# I2C_EEPROM.net
KiCad netlist of a schematic drawn in Altium Designer
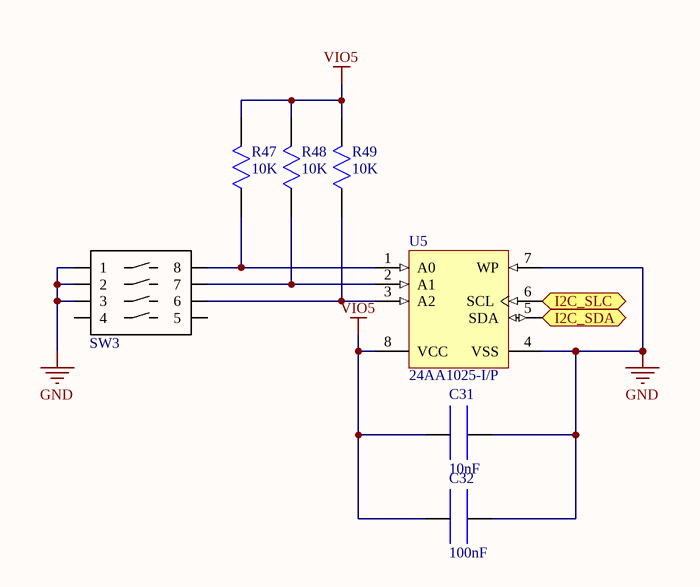
[diagram p0: I2C_EEPROM.SchDoc]

(export (version "E")
  (design (tool "Eeschema 10.0.6"))
  (components
    (comp (ref "C31")
      (value "10nF")
      (footprint "SMD Capacitor 0603")
      (fields (field (name "Comment") "Capacitor"))
      (libsource (lib "DA_Component_Library") (part "Capacitor"))
    )
    (comp (ref "C32")
      (value "100nF")
      (footprint "SMD Capacitor 0603")
      (fields (field (name "Comment") "Capacitor"))
      (libsource (lib "DA_Component_Library") (part "Capacitor"))
    )
    (comp (ref "R47")
      (value "10K")
      (footprint "SMD Resistor 0603")
      (fields (field (name "Comment") "Resistor"))
      (libsource (lib "DA_Component_Library") (part "Resistor"))
    )
    (comp (ref "R48")
      (value "10K")
      (footprint "SMD Resistor 0603")
      (fields (field (name "Comment") "Resistor"))
      (libsource (lib "DA_Component_Library") (part "Resistor"))
    )
    (comp (ref "R49")
      (value "10K")
      (footprint "SMD Resistor 0603")
      (fields (field (name "Comment") "Resistor"))
      (libsource (lib "DA_Component_Library") (part "Resistor"))
    )
    (comp (ref "SW3")
      (value "SW_DIP_4Position")
      (footprint "218-4LPST")
      (libsource (lib "DA_Component_Library") (part "SW_DIP_4Position"))
    )
    (comp (ref "U5")
      (value "24AA1025-I/P")
      (footprint "PDIP300-P8")
      (description "1 Mbit, 400kHz, 1.7V, I2C Serial EEPROM, 8-Pin PDIP, Industrial Temperature")
      (fields (field (name "MANUFACTURER") "Microchip"))
      (libsource (lib "Microchip I2C Serial EEPROM") (part "24AA1025-I/P"))
    )
  )
  (nets
    (net (code "1") (name "/I2C_SDA") (class "Default")
      (node (ref "U5") (pin "5") (pinfunction "SDA_5") (pintype "bidirectional"))
    )
    (net (code "2") (name "/I2C_SLC") (class "Default")
      (node (ref "U5") (pin "6") (pinfunction "SCL_6") (pintype "input"))
    )
    (net (code "3") (name "GND") (class "Default")
      (node (ref "C31") (pin "1") (pinfunction "1_1") (pintype "passive"))
      (node (ref "C32") (pin "1") (pinfunction "1_1") (pintype "passive"))
      (node (ref "SW3") (pin "1") (pinfunction "1_1") (pintype "passive"))
      (node (ref "SW3") (pin "2") (pinfunction "2_2") (pintype "passive"))
      (node (ref "SW3") (pin "3") (pinfunction "3_3") (pintype "passive"))
      (node (ref "U5") (pin "4") (pinfunction "VSS_4") (pintype "power_in"))
      (node (ref "U5") (pin "7") (pinfunction "WP_7") (pintype "input"))
    )
    (net (code "4") (name "Net-(U5-A0)") (class "Default")
      (node (ref "R47") (pin "0") (pinfunction "0_0") (pintype "passive"))
      (node (ref "SW3") (pin "8") (pinfunction "8_8") (pintype "passive"))
      (node (ref "U5") (pin "1") (pinfunction "A0_1") (pintype "input"))
    )
    (net (code "5") (name "Net-(U5-A1)") (class "Default")
      (node (ref "R48") (pin "0") (pinfunction "0_0") (pintype "passive"))
      (node (ref "SW3") (pin "7") (pinfunction "7_7") (pintype "passive"))
      (node (ref "U5") (pin "2") (pinfunction "A1_2") (pintype "input"))
    )
    (net (code "6") (name "Net-(U5-A2)") (class "Default")
      (node (ref "R49") (pin "0") (pinfunction "0_0") (pintype "passive"))
      (node (ref "SW3") (pin "6") (pinfunction "6_6") (pintype "passive"))
      (node (ref "U5") (pin "3") (pinfunction "A2_3") (pintype "input"))
    )
    (net (code "7") (name "VIO5") (class "Default")
      (node (ref "C31") (pin "0") (pinfunction "0_0") (pintype "passive"))
      (node (ref "C32") (pin "0") (pinfunction "0_0") (pintype "passive"))
      (node (ref "R47") (pin "1") (pinfunction "1_1") (pintype "passive"))
      (node (ref "R48") (pin "1") (pinfunction "1_1") (pintype "passive"))
      (node (ref "R49") (pin "1") (pinfunction "1_1") (pintype "passive"))
      (node (ref "U5") (pin "8") (pinfunction "VCC_8") (pintype "power_in"))
    )
    (net (code "8") (name "unconnected-(SW3-Pad4)") (class "Default")
      (node (ref "SW3") (pin "4") (pinfunction "4_4") (pintype "passive"))
    )
    (net (code "9") (name "unconnected-(SW3-Pad5)") (class "Default")
      (node (ref "SW3") (pin "5") (pinfunction "5_5") (pintype "passive"))
    )
  )
)
